# NES_IO.net
KiCad netlist of a schematic drawn in EAGLE
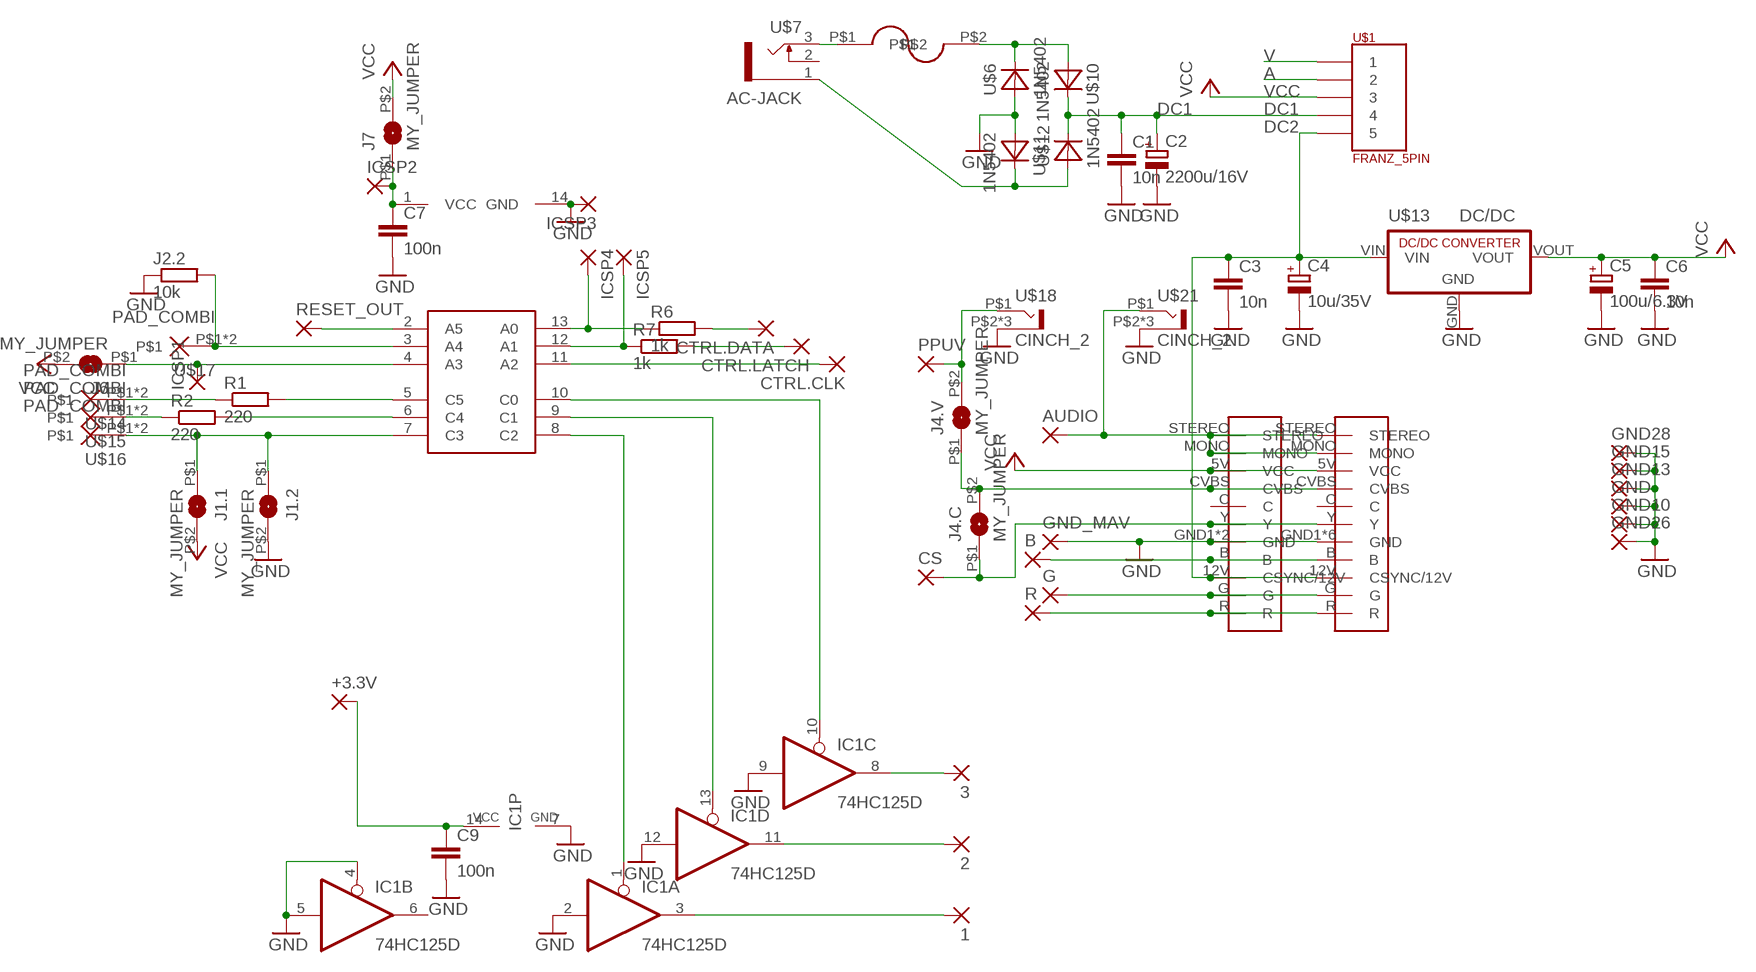
[diagram p0: schematic, sheet 1]

(export (version "E")
  (design (tool "Eeschema 10.0.6"))
  (components
    (comp (ref "+3.3V")
      (value "SMD2")
      (footprint "eagle-import:SMD1,27-2,54")
      (libsource (lib "eagle-import") (part "SMD2"))
    )
    (comp (ref "1")
      (value "SMD2")
      (footprint "eagle-import:SMD1,27-2,54")
      (libsource (lib "eagle-import") (part "SMD2"))
    )
    (comp (ref "2")
      (value "SMD2")
      (footprint "eagle-import:SMD1,27-2,54")
      (libsource (lib "eagle-import") (part "SMD2"))
    )
    (comp (ref "3")
      (value "SMD2")
      (footprint "eagle-import:SMD1,27-2,54")
      (libsource (lib "eagle-import") (part "SMD2"))
    )
    (comp (ref "AUDIO")
      (value "SMD2")
      (footprint "eagle-import:SMD1,27-2,54")
      (libsource (lib "eagle-import") (part "SMD2"))
    )
    (comp (ref "B")
      (value "SMD2")
      (footprint "eagle-import:SMD1,27-2,54")
      (libsource (lib "eagle-import") (part "SMD2"))
    )
    (comp (ref "C1")
      (value "10n")
      (footprint "eagle-import:Z0805")
      (libsource (lib "eagle-import") (part "C0805"))
    )
    (comp (ref "C2")
      (value "2200u/16V")
      (footprint "eagle-import:E5-13")
      (libsource (lib "eagle-import") (part "resistor_CPOL-EUE5-13"))
    )
    (comp (ref "C3")
      (value "10n")
      (footprint "eagle-import:Z0805")
      (libsource (lib "eagle-import") (part "C0805"))
    )
    (comp (ref "C4")
      (value "10u/35V")
      (footprint "eagle-import:PANASONIC_B")
      (libsource (lib "eagle-import") (part "CPOL-EUB"))
    )
    (comp (ref "C5")
      (value "100u/6.3V")
      (footprint "eagle-import:PANASONIC_D")
      (libsource (lib "eagle-import") (part "CPOL-EUD"))
    )
    (comp (ref "C6")
      (value "10n")
      (footprint "eagle-import:Z0805")
      (libsource (lib "eagle-import") (part "C0805"))
    )
    (comp (ref "C7")
      (value "100n")
      (footprint "eagle-import:Z0805")
      (libsource (lib "eagle-import") (part "C0805"))
    )
    (comp (ref "C9")
      (value "100n")
      (footprint "eagle-import:Z0805")
      (libsource (lib "eagle-import") (part "C0805"))
    )
    (comp (ref "CS")
      (value "SMD2")
      (footprint "eagle-import:SMD1,27-2,54")
      (libsource (lib "eagle-import") (part "SMD2"))
    )
    (comp (ref "CTRL.CLK")
      (value "SMD2")
      (footprint "eagle-import:SMD1,27-2,54")
      (libsource (lib "eagle-import") (part "SMD2"))
    )
    (comp (ref "CTRL.DATA")
      (value "SMD2")
      (footprint "eagle-import:SMD1,27-2,54")
      (libsource (lib "eagle-import") (part "SMD2"))
    )
    (comp (ref "CTRL.LATCH")
      (value "SMD2")
      (footprint "eagle-import:SMD1,27-2,54")
      (libsource (lib "eagle-import") (part "SMD2"))
    )
    (comp (ref "G")
      (value "SMD2")
      (footprint "eagle-import:SMD1,27-2,54")
      (libsource (lib "eagle-import") (part "SMD2"))
    )
    (comp (ref "GND")
      (value "SMD5")
      (footprint "eagle-import:SMD2,54-5,08")
      (libsource (lib "eagle-import") (part "SMD5"))
    )
    (comp (ref "GND10")
      (value "SMD5")
      (footprint "eagle-import:SMD2,54-5,08")
      (libsource (lib "eagle-import") (part "SMD5"))
    )
    (comp (ref "GND13")
      (value "SMD5")
      (footprint "eagle-import:SMD2,54-5,08")
      (libsource (lib "eagle-import") (part "SMD5"))
    )
    (comp (ref "GND15")
      (value "SMD5")
      (footprint "eagle-import:SMD2,54-5,08")
      (libsource (lib "eagle-import") (part "SMD5"))
    )
    (comp (ref "GND26")
      (value "SMD5")
      (footprint "eagle-import:SMD2,54-5,08")
      (libsource (lib "eagle-import") (part "SMD5"))
    )
    (comp (ref "GND28")
      (value "SMD5")
      (footprint "eagle-import:SMD2,54-5,08")
      (libsource (lib "eagle-import") (part "SMD5"))
    )
    (comp (ref "GND_MAV")
      (value "SMD2")
      (footprint "eagle-import:SMD1,27-2,54")
      (libsource (lib "eagle-import") (part "SMD2"))
    )
    (comp (ref "IC1")
      (value "74HC125D")
      (footprint "eagle-import:SO14")
      (libsource (lib "eagle-import") (part "74125DHC"))
    )
    (comp (ref "ICSP1")
      (value "1,6/0,8")
      (footprint "eagle-import:1,6_0,8")
      (libsource (lib "eagle-import") (part "1,6/0,8"))
    )
    (comp (ref "ICSP2")
      (value "1,6/0,8")
      (footprint "eagle-import:1,6_0,8")
      (libsource (lib "eagle-import") (part "1,6/0,8"))
    )
    (comp (ref "ICSP3")
      (value "1,6/0,8")
      (footprint "eagle-import:1,6_0,8")
      (libsource (lib "eagle-import") (part "1,6/0,8"))
    )
    (comp (ref "ICSP4")
      (value "1,6/0,8")
      (footprint "eagle-import:1,6_0,8")
      (libsource (lib "eagle-import") (part "1,6/0,8"))
    )
    (comp (ref "ICSP5")
      (value "1,6/0,8")
      (footprint "eagle-import:1,6_0,8")
      (libsource (lib "eagle-import") (part "1,6/0,8"))
    )
    (comp (ref "J1.1")
      (value "MY_JUMPER")
      (footprint "eagle-import:MYJUMP")
      (libsource (lib "eagle-import") (part "MY_JUMPER"))
    )
    (comp (ref "J1.2")
      (value "MY_JUMPER")
      (footprint "eagle-import:MYJUMP")
      (libsource (lib "eagle-import") (part "MY_JUMPER"))
    )
    (comp (ref "J2.2")
      (value "10k")
      (footprint "eagle-import:Z0805")
      (libsource (lib "eagle-import") (part "R0805"))
    )
    (comp (ref "J4.C")
      (value "MY_JUMPER")
      (footprint "eagle-import:MYJUMP")
      (libsource (lib "eagle-import") (part "MY_JUMPER"))
    )
    (comp (ref "J4.V")
      (value "MY_JUMPER")
      (footprint "eagle-import:MYJUMP")
      (libsource (lib "eagle-import") (part "MY_JUMPER"))
    )
    (comp (ref "J6")
      (value "MY_JUMPER")
      (footprint "eagle-import:MYJUMP")
      (libsource (lib "eagle-import") (part "MY_JUMPER"))
    )
    (comp (ref "J7")
      (value "MY_JUMPER")
      (footprint "eagle-import:MYJUMP")
      (libsource (lib "eagle-import") (part "MY_JUMPER"))
    )
    (comp (ref "PPUV")
      (value "SMD2")
      (footprint "eagle-import:SMD1,27-2,54")
      (libsource (lib "eagle-import") (part "SMD2"))
    )
    (comp (ref "R")
      (value "SMD2")
      (footprint "eagle-import:SMD1,27-2,54")
      (libsource (lib "eagle-import") (part "SMD2"))
    )
    (comp (ref "R1")
      (value "220")
      (footprint "eagle-import:Z0805")
      (libsource (lib "eagle-import") (part "R0805"))
    )
    (comp (ref "R2")
      (value "220")
      (footprint "eagle-import:Z0805")
      (libsource (lib "eagle-import") (part "R0805"))
    )
    (comp (ref "R6")
      (value "1k")
      (footprint "eagle-import:Z0805")
      (libsource (lib "eagle-import") (part "R0805"))
    )
    (comp (ref "R7")
      (value "1k")
      (footprint "eagle-import:Z0805")
      (libsource (lib "eagle-import") (part "R0805"))
    )
    (comp (ref "RESET_OUT")
      (value "SMD2")
      (footprint "eagle-import:SMD1,27-2,54")
      (libsource (lib "eagle-import") (part "SMD2"))
    )
    (comp (ref "U$1")
      (value "FRANZ_5PIN")
      (footprint "eagle-import:5X2.22RM4")
      (libsource (lib "eagle-import") (part "FRANZ_5PIN"))
    )
    (comp (ref "U$2")
      (value "FUSEHOLDER")
      (footprint "eagle-import:FUSEHOLDER")
      (libsource (lib "eagle-import") (part "FUSEHOLDER"))
    )
    (comp (ref "U$5")
      (value "PIC16F630_SIMPLE")
      (footprint "eagle-import:PIC16F630")
      (libsource (lib "eagle-import") (part "PIC16F630_SIMPLE"))
    )
    (comp (ref "U$6")
      (value "1N5402")
      (footprint "eagle-import:DO201")
      (libsource (lib "eagle-import") (part "1N5402"))
    )
    (comp (ref "U$7")
      (value "AC-JACK")
      (footprint "eagle-import:AC-JACK")
      (libsource (lib "eagle-import") (part "AC-JACK"))
    )
    (comp (ref "U$10")
      (value "1N5402")
      (footprint "eagle-import:DO201")
      (libsource (lib "eagle-import") (part "1N5402"))
    )
    (comp (ref "U$11")
      (value "1N5402")
      (footprint "eagle-import:DO201")
      (libsource (lib "eagle-import") (part "1N5402"))
    )
    (comp (ref "U$12")
      (value "1N5402")
      (footprint "eagle-import:DO201")
      (libsource (lib "eagle-import") (part "1N5402"))
    )
    (comp (ref "U$13")
      (value "DC/DC")
      (footprint "eagle-import:RECOM")
      (libsource (lib "eagle-import") (part "DC/DC"))
    )
    (comp (ref "U$14")
      (value "PAD_COMBI")
      (footprint "eagle-import:PAD_COMBI")
      (libsource (lib "eagle-import") (part "PAD_COMBI"))
    )
    (comp (ref "U$15")
      (value "PAD_COMBI")
      (footprint "eagle-import:PAD_COMBI")
      (libsource (lib "eagle-import") (part "PAD_COMBI"))
    )
    (comp (ref "U$16")
      (value "PAD_COMBI")
      (footprint "eagle-import:PAD_COMBI")
      (libsource (lib "eagle-import") (part "PAD_COMBI"))
    )
    (comp (ref "U$17")
      (value "PAD_COMBI")
      (footprint "eagle-import:PAD_COMBI")
      (libsource (lib "eagle-import") (part "PAD_COMBI"))
    )
    (comp (ref "U$18")
      (value "CINCH_2")
      (footprint "eagle-import:CINCH_2")
      (libsource (lib "eagle-import") (part "CINCH_2"))
    )
    (comp (ref "U$19")
      (value "GC-MULTIAV")
      (footprint "eagle-import:GC-MULTIAV")
      (libsource (lib "eagle-import") (part "GC-MULTIAV"))
    )
    (comp (ref "U$20")
      (value "SNES-MULTIAV2")
      (footprint "eagle-import:SNES-MULTIAV2")
      (libsource (lib "eagle-import") (part "SNES-MULTIAV2"))
    )
    (comp (ref "U$21")
      (value "CINCH_2")
      (footprint "eagle-import:CINCH_2")
      (libsource (lib "eagle-import") (part "CINCH_2"))
    )
  )
  (nets
    (net (code "1") (name "/A") (class "Default")
      (node (ref "U$1") (pin "P$2") (pinfunction "2_P$2") (pintype "bidirectional"))
    )
    (net (code "2") (name "/DC1") (class "Default")
      (node (ref "C1") (pin "1") (pinfunction "1_1") (pintype "passive"))
      (node (ref "C2") (pin "+") (pinfunction "+_+") (pintype "passive"))
      (node (ref "U$1") (pin "P$4") (pinfunction "4_P$4") (pintype "bidirectional"))
      (node (ref "U$10") (pin "C") (pinfunction "C_C") (pintype "passive"))
      (node (ref "U$12") (pin "C") (pinfunction "C_C") (pintype "passive"))
    )
    (net (code "3") (name "/DC2") (class "Default")
      (node (ref "C3") (pin "1") (pinfunction "1_1") (pintype "passive"))
      (node (ref "C4") (pin "+") (pinfunction "+_+") (pintype "passive"))
      (node (ref "U$1") (pin "P$5") (pinfunction "5_P$5") (pintype "bidirectional"))
      (node (ref "U$13") (pin "VIN") (pinfunction "VIN_VIN") (pintype "passive"))
      (node (ref "U$19") (pin "12V") (pinfunction "CSYNC/12V_12V") (pintype "output"))
      (node (ref "U$20") (pin "12V") (pinfunction "CSYNC/12V_12V") (pintype "output"))
    )
    (net (code "4") (name "/V") (class "Default")
      (node (ref "U$1") (pin "P$1") (pinfunction "1_P$1") (pintype "bidirectional"))
    )
    (net (code "5") (name "GND") (class "Default")
      (node (ref "C1") (pin "2") (pinfunction "2_2") (pintype "passive"))
      (node (ref "C2") (pin "-") (pinfunction "-_-") (pintype "passive"))
      (node (ref "C3") (pin "2") (pinfunction "2_2") (pintype "passive"))
      (node (ref "C4") (pin "-") (pinfunction "-_-") (pintype "passive"))
      (node (ref "C5") (pin "-") (pinfunction "-_-") (pintype "passive"))
      (node (ref "C6") (pin "2") (pinfunction "2_2") (pintype "passive"))
      (node (ref "C7") (pin "2") (pinfunction "2_2") (pintype "passive"))
      (node (ref "C9") (pin "2") (pinfunction "2_2") (pintype "passive"))
      (node (ref "GND") (pin "1") (pinfunction "P_1") (pintype "passive"))
      (node (ref "GND10") (pin "1") (pinfunction "P_1") (pintype "passive"))
      (node (ref "GND13") (pin "1") (pinfunction "P_1") (pintype "passive"))
      (node (ref "GND15") (pin "1") (pinfunction "P_1") (pintype "passive"))
      (node (ref "GND26") (pin "1") (pinfunction "P_1") (pintype "passive"))
      (node (ref "GND28") (pin "1") (pinfunction "P_1") (pintype "passive"))
      (node (ref "GND_MAV") (pin "1") (pinfunction "P_1") (pintype "passive"))
      (node (ref "IC1") (pin "12") (pinfunction "I_12") (pintype "input"))
      (node (ref "IC1") (pin "2") (pinfunction "I_2") (pintype "input"))
      (node (ref "IC1") (pin "4") (pinfunction "OE_4") (pintype "input"))
      (node (ref "IC1") (pin "5") (pinfunction "I_5") (pintype "input"))
      (node (ref "IC1") (pin "7") (pinfunction "GND_7") (pintype "power_in"))
      (node (ref "IC1") (pin "9") (pinfunction "I_9") (pintype "input"))
      (node (ref "ICSP3") (pin "1") (pinfunction "P_1") (pintype "passive"))
      (node (ref "J1.2") (pin "P$2") (pinfunction "2_P$2") (pintype "passive"))
      (node (ref "J2.2") (pin "1") (pinfunction "1_1") (pintype "passive"))
      (node (ref "U$11") (pin "A") (pinfunction "A_A") (pintype "passive"))
      (node (ref "U$13") (pin "GND") (pinfunction "GND_GND") (pintype "passive"))
      (node (ref "U$18") (pin "P$2") (pinfunction "S_P$2") (pintype "passive"))
      (node (ref "U$18") (pin "P$3") (pinfunction "S_P$3") (pintype "passive"))
      (node (ref "U$18") (pin "P$4") (pinfunction "S_P$4") (pintype "passive"))
      (node (ref "U$19") (pin "GND1") (pinfunction "GND_GND1") (pintype "output"))
      (node (ref "U$19") (pin "GND2") (pinfunction "GND_GND2") (pintype "output"))
      (node (ref "U$19") (pin "GND3") (pinfunction "GND_GND3") (pintype "output"))
      (node (ref "U$19") (pin "GND4") (pinfunction "GND_GND4") (pintype "output"))
      (node (ref "U$19") (pin "GND5") (pinfunction "GND_GND5") (pintype "output"))
      (node (ref "U$19") (pin "GND6") (pinfunction "GND_GND6") (pintype "output"))
      (node (ref "U$20") (pin "GND1") (pinfunction "GND_GND1") (pintype "output"))
      (node (ref "U$20") (pin "GND2") (pinfunction "GND_GND2") (pintype "output"))
      (node (ref "U$21") (pin "P$2") (pinfunction "S_P$2") (pintype "passive"))
      (node (ref "U$21") (pin "P$3") (pinfunction "S_P$3") (pintype "passive"))
      (node (ref "U$21") (pin "P$4") (pinfunction "S_P$4") (pintype "passive"))
      (node (ref "U$5") (pin "14") (pinfunction "GND_14") (pintype "bidirectional"))
      (node (ref "U$6") (pin "A") (pinfunction "A_A") (pintype "passive"))
    )
    (net (code "6") (name "Net-(+3.3V-P)") (class "Default")
      (node (ref "+3.3V") (pin "1") (pinfunction "P_1") (pintype "passive"))
      (node (ref "C9") (pin "1") (pinfunction "1_1") (pintype "passive"))
      (node (ref "IC1") (pin "14") (pinfunction "VCC_14") (pintype "power_in"))
    )
    (net (code "7") (name "Net-(1-P)") (class "Default")
      (node (ref "1") (pin "1") (pinfunction "P_1") (pintype "passive"))
      (node (ref "IC1") (pin "3") (pinfunction "O_3") (pintype "tri_state"))
    )
    (net (code "8") (name "Net-(2-P)") (class "Default")
      (node (ref "2") (pin "1") (pinfunction "P_1") (pintype "passive"))
      (node (ref "IC1") (pin "11") (pinfunction "O_11") (pintype "tri_state"))
    )
    (net (code "9") (name "Net-(3-P)") (class "Default")
      (node (ref "3") (pin "1") (pinfunction "P_1") (pintype "passive"))
      (node (ref "IC1") (pin "8") (pinfunction "O_8") (pintype "tri_state"))
    )
    (net (code "10") (name "Net-(AUDIO-P)") (class "Default")
      (node (ref "AUDIO") (pin "1") (pinfunction "P_1") (pintype "passive"))
      (node (ref "U$19") (pin "MONO") (pinfunction "MONO_MONO") (pintype "output"))
      (node (ref "U$19") (pin "STEREO") (pinfunction "STEREO_STEREO") (pintype "output"))
      (node (ref "U$20") (pin "MONO") (pinfunction "MONO_MONO") (pintype "output"))
      (node (ref "U$20") (pin "STEREO") (pinfunction "STEREO_STEREO") (pintype "output"))
      (node (ref "U$21") (pin "P$1") (pinfunction "T_P$1") (pintype "passive"))
    )
    (net (code "11") (name "Net-(B-P)") (class "Default")
      (node (ref "B") (pin "1") (pinfunction "P_1") (pintype "passive"))
      (node (ref "U$19") (pin "B") (pinfunction "B_B") (pintype "output"))
      (node (ref "U$20") (pin "B") (pinfunction "B_B") (pintype "output"))
    )
    (net (code "12") (name "Net-(CS-P)") (class "Default")
      (node (ref "CS") (pin "1") (pinfunction "P_1") (pintype "passive"))
      (node (ref "J4.C") (pin "P$1") (pinfunction "1_P$1") (pintype "passive"))
      (node (ref "U$19") (pin "Y") (pinfunction "Y_Y") (pintype "output"))
      (node (ref "U$20") (pin "Y") (pinfunction "Y_Y") (pintype "output"))
    )
    (net (code "13") (name "Net-(CTRL.CLK-P)") (class "Default")
      (node (ref "CTRL.CLK") (pin "1") (pinfunction "P_1") (pintype "passive"))
      (node (ref "U$5") (pin "11") (pinfunction "A2_11") (pintype "bidirectional"))
    )
    (net (code "14") (name "Net-(CTRL.DATA-P)") (class "Default")
      (node (ref "CTRL.DATA") (pin "1") (pinfunction "P_1") (pintype "passive"))
      (node (ref "R6") (pin "2") (pinfunction "2_2") (pintype "passive"))
    )
    (net (code "15") (name "Net-(CTRL.LATCH-P)") (class "Default")
      (node (ref "CTRL.LATCH") (pin "1") (pinfunction "P_1") (pintype "passive"))
      (node (ref "R7") (pin "2") (pinfunction "2_2") (pintype "passive"))
    )
    (net (code "16") (name "Net-(G-P)") (class "Default")
      (node (ref "G") (pin "1") (pinfunction "P_1") (pintype "passive"))
      (node (ref "U$19") (pin "G") (pinfunction "G_G") (pintype "output"))
      (node (ref "U$20") (pin "G") (pinfunction "G_G") (pintype "output"))
    )
    (net (code "17") (name "Net-(IC1A-OE)") (class "Default")
      (node (ref "IC1") (pin "1") (pinfunction "OE_1") (pintype "input"))
      (node (ref "U$5") (pin "8") (pinfunction "C2_8") (pintype "bidirectional"))
    )
    (net (code "18") (name "Net-(IC1C-OE)") (class "Default")
      (node (ref "IC1") (pin "10") (pinfunction "OE_10") (pintype "input"))
      (node (ref "U$5") (pin "10") (pinfunction "C0_10") (pintype "bidirectional"))
    )
    (net (code "19") (name "Net-(IC1D-OE)") (class "Default")
      (node (ref "IC1") (pin "13") (pinfunction "OE_13") (pintype "input"))
      (node (ref "U$5") (pin "9") (pinfunction "C1_9") (pintype "bidirectional"))
    )
    (net (code "20") (name "Net-(ICSP1-P)") (class "Default")
      (node (ref "ICSP1") (pin "1") (pinfunction "P_1") (pintype "passive"))
      (node (ref "J6") (pin "P$1") (pinfunction "1_P$1") (pintype "passive"))
      (node (ref "U$5") (pin "4") (pinfunction "A3_4") (pintype "bidirectional"))
    )
    (net (code "21") (name "Net-(ICSP2-P)") (class "Default")
      (node (ref "C7") (pin "1") (pinfunction "1_1") (pintype "passive"))
      (node (ref "ICSP2") (pin "1") (pinfunction "P_1") (pintype "passive"))
      (node (ref "J7") (pin "P$1") (pinfunction "1_P$1") (pintype "passive"))
      (node (ref "U$5") (pin "1") (pinfunction "VCC_1") (pintype "bidirectional"))
    )
    (net (code "22") (name "Net-(ICSP4-P)") (class "Default")
      (node (ref "ICSP4") (pin "1") (pinfunction "P_1") (pintype "passive"))
      (node (ref "R6") (pin "1") (pinfunction "1_1") (pintype "passive"))
      (node (ref "U$5") (pin "13") (pinfunction "A0_13") (pintype "bidirectional"))
    )
    (net (code "23") (name "Net-(ICSP5-P)") (class "Default")
      (node (ref "ICSP5") (pin "1") (pinfunction "P_1") (pintype "passive"))
      (node (ref "R7") (pin "1") (pinfunction "1_1") (pintype "passive"))
      (node (ref "U$5") (pin "12") (pinfunction "A1_12") (pintype "bidirectional"))
    )
    (net (code "24") (name "Net-(J1.1-1)") (class "Default")
      (node (ref "J1.1") (pin "P$1") (pinfunction "1_P$1") (pintype "passive"))
      (node (ref "J1.2") (pin "P$1") (pinfunction "1_P$1") (pintype "passive"))
      (node (ref "U$16") (pin "P$1") (pinfunction "P$1_P$1") (pintype "bidirectional"))
      (node (ref "U$16") (pin "P$2") (pinfunction "P$1_P$2") (pintype "bidirectional"))
      (node (ref "U$5") (pin "7") (pinfunction "C3_7") (pintype "bidirectional"))
    )
    (net (code "25") (name "Net-(J4.C-2)") (class "Default")
      (node (ref "J4.C") (pin "P$2") (pinfunction "2_P$2") (pintype "passive"))
      (node (ref "J4.V") (pin "P$1") (pinfunction "1_P$1") (pintype "passive"))
      (node (ref "U$19") (pin "CVBS") (pinfunction "CVBS_CVBS") (pintype "output"))
      (node (ref "U$20") (pin "CVBS") (pinfunction "CVBS_CVBS") (pintype "output"))
    )
    (net (code "26") (name "Net-(J4.V-2)") (class "Default")
      (node (ref "J4.V") (pin "P$2") (pinfunction "2_P$2") (pintype "passive"))
      (node (ref "PPUV") (pin "1") (pinfunction "P_1") (pintype "passive"))
      (node (ref "U$18") (pin "P$1") (pinfunction "T_P$1") (pintype "passive"))
    )
    (net (code "27") (name "Net-(R-P)") (class "Default")
      (node (ref "R") (pin "1") (pinfunction "P_1") (pintype "passive"))
      (node (ref "U$19") (pin "R") (pinfunction "R_R") (pintype "output"))
      (node (ref "U$20") (pin "R") (pinfunction "R_R") (pintype "output"))
    )
    (net (code "28") (name "Net-(R1-Pad1)") (class "Default")
      (node (ref "R1") (pin "1") (pinfunction "1_1") (pintype "passive"))
      (node (ref "U$14") (pin "P$1") (pinfunction "P$1_P$1") (pintype "bidirectional"))
      (node (ref "U$14") (pin "P$2") (pinfunction "P$1_P$2") (pintype "bidirectional"))
    )
    (net (code "29") (name "Net-(R2-Pad1)") (class "Default")
      (node (ref "R2") (pin "1") (pinfunction "1_1") (pintype "passive"))
      (node (ref "U$15") (pin "P$1") (pinfunction "P$1_P$1") (pintype "bidirectional"))
      (node (ref "U$15") (pin "P$2") (pinfunction "P$1_P$2") (pintype "bidirectional"))
    )
    (net (code "30") (name "Net-(RESET_OUT-P)") (class "Default")
      (node (ref "RESET_OUT") (pin "1") (pinfunction "P_1") (pintype "passive"))
      (node (ref "U$5") (pin "2") (pinfunction "A5_2") (pintype "bidirectional"))
    )
    (net (code "31") (name "Net-(U$2-PadP$1)") (class "Default")
      (node (ref "U$2") (pin "P$1") (pinfunction "P$1_P$1") (pintype "bidirectional"))
      (node (ref "U$7") (pin "3") (pinfunction "3_3") (pintype "passive"))
    )
    (net (code "32") (name "Net-(U$5A-A4)") (class "Default")
      (node (ref "J2.2") (pin "2") (pinfunction "2_2") (pintype "passive"))
      (node (ref "U$17") (pin "P$1") (pinfunction "P$1_P$1") (pintype "bidirectional"))
      (node (ref "U$17") (pin "P$2") (pinfunction "P$1_P$2") (pintype "bidirectional"))
      (node (ref "U$5") (pin "3") (pinfunction "A4_3") (pintype "bidirectional"))
    )
    (net (code "33") (name "Net-(U$5A-C4)") (class "Default")
      (node (ref "R2") (pin "2") (pinfunction "2_2") (pintype "passive"))
      (node (ref "U$5") (pin "6") (pinfunction "C4_6") (pintype "bidirectional"))
    )
    (net (code "34") (name "Net-(U$5A-C5)") (class "Default")
      (node (ref "R1") (pin "2") (pinfunction "2_2") (pintype "passive"))
      (node (ref "U$5") (pin "5") (pinfunction "C5_5") (pintype "bidirectional"))
    )
    (net (code "35") (name "Net-(U$7-5)") (class "Default")
      (node (ref "U$11") (pin "C") (pinfunction "C_C") (pintype "passive"))
      (node (ref "U$12") (pin "A") (pinfunction "A_A") (pintype "passive"))
      (node (ref "U$7") (pin "1") (pinfunction "5_1") (pintype "passive"))
    )
    (net (code "36") (name "Net-(U$10-PadA)") (class "Default")
      (node (ref "U$10") (pin "A") (pinfunction "A_A") (pintype "passive"))
      (node (ref "U$2") (pin "P$2") (pinfunction "P$2_P$2") (pintype "bidirectional"))
      (node (ref "U$6") (pin "C") (pinfunction "C_C") (pintype "passive"))
    )
    (net (code "37") (name "VCC") (class "Default")
      (node (ref "C5") (pin "+") (pinfunction "+_+") (pintype "passive"))
      (node (ref "C6") (pin "1") (pinfunction "1_1") (pintype "passive"))
      (node (ref "J1.1") (pin "P$2") (pinfunction "2_P$2") (pintype "passive"))
      (node (ref "J6") (pin "P$2") (pinfunction "2_P$2") (pintype "passive"))
      (node (ref "J7") (pin "P$2") (pinfunction "2_P$2") (pintype "passive"))
      (node (ref "U$1") (pin "P$3") (pinfunction "3_P$3") (pintype "bidirectional"))
      (node (ref "U$13") (pin "VOUT") (pinfunction "VOUT_VOUT") (pintype "passive"))
      (node (ref "U$19") (pin "5V") (pinfunction "VCC_5V") (pintype "output"))
      (node (ref "U$20") (pin "5V") (pinfunction "VCC_5V") (pintype "output"))
    )
    (net (code "38") (name "unconnected-(IC1B-O-Pad6)") (class "Default")
      (node (ref "IC1") (pin "6") (pinfunction "O_6") (pintype "tri_state"))
    )
    (net (code "39") (name "unconnected-(U$7-4-Pad2)") (class "Default")
      (node (ref "U$7") (pin "2") (pinfunction "4_2") (pintype "passive"))
    )
    (net (code "40") (name "unconnected-(U$19-PadC)") (class "Default")
      (node (ref "U$19") (pin "C") (pinfunction "C_C") (pintype "output"))
    )
    (net (code "41") (name "unconnected-(U$20-PadC)") (class "Default")
      (node (ref "U$20") (pin "C") (pinfunction "C_C") (pintype "output"))
    )
  )
)
